# FontesLineares.net
KiCad netlist of a schematic drawn in Altium Designer
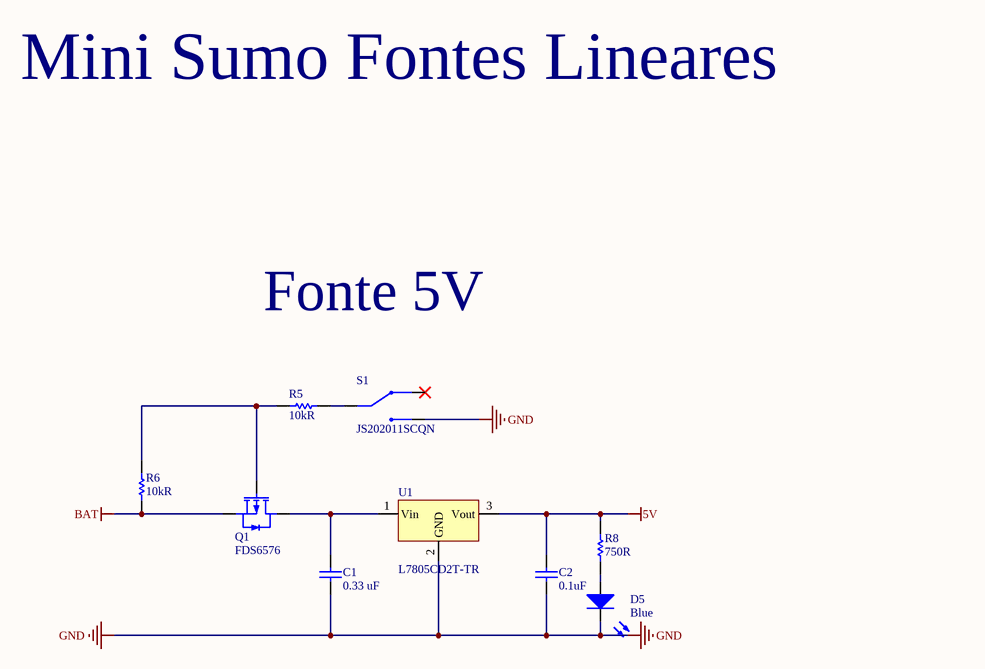
[diagram p0: FontesLineares.SchDoc]

(export (version "E")
  (design (tool "Eeschema 10.0.6"))
  (components
    (comp (ref "C1")
      (value "0.33 uF")
      (footprint "C0805")
      (description "CAP CER 0.33UF 25V X7R 0805")
      (fields
        (field (name "MANUFACTURER") "Murata Eletronics")
        (field (name "PART NUMBER") "GCM21BR71E334KA37K")
        (field (name "LIBRARY CONTROL - PERSON THAT CHECKED FOOTPRINT") "Nikaum")
        (field (name "LIBRARY CONTROL - PERSON THAT CHECKED SCHEMATIC") "Nikaum")
        (field (name "LIBRARY CONTROL - PERSON THAT DID THE LAST UPDATE FOOTPRINT") "Nikaum")
        (field (name "LIBRARY CONTROL - PERSON THAT DID THE LAST UPDATE SCHEMATIC") "Nikaum")
      )
      (libsource (lib "Uai!Tecas") (part "GCM21BR71E334KA37K"))
    )
    (comp (ref "C2")
      (value "0.1uF")
      (footprint "C0805")
      (description "CAP CER 0.1uF 25V X7R 0805")
      (fields
        (field (name "MANUFACTURER") "Kemet")
        (field (name "PART NUMBER") "C0805C104M3RACTU")
        (field (name "LIBRARY CONTROL - PERSON THAT CHECKED SCHEMATIC") "Guilherme")
        (field (name "LIBRARY CONTROL - PERSON THAT DID THE LAST UPDATE SCHEMATIC") "Marcos")
      )
      (libsource (lib "Uai!Tecas") (part "C0805C104M3RACTU"))
    )
    (comp (ref "D5")
      (value "Blue")
      (footprint "DIODO_2-SMD-3215")
      (description "LED 75mW BLUE 45MCD 3215")
      (fields
        (field (name "MANUFACTURER") "Everlight Electronics")
        (field (name "PART NUMBER") "EAST3215BA5")
        (field (name "LIBRARY CONTROL - PERSON THAT CHECKED FOOTPRINT") "Lucas")
        (field (name "LIBRARY CONTROL - PERSON THAT CHECKED SCHEMATIC") "Lucas")
        (field (name "LIBRARY CONTROL - PERSON THAT DID THE LAST UPDATE FOOTPRINT") "Stéfany (Ster)")
        (field (name "LIBRARY CONTROL - PERSON THAT DID THE LAST UPDATE SCHEMATIC") "Stéfany (Ster)")
      )
      (libsource (lib "Diodo") (part "EAST3215BA5"))
    )
    (comp (ref "Q1")
      (value "FDS6576")
      (footprint "SOIC-8")
      (description "MOSFET P-CH 20V 11A SOIC-8")
      (fields (field (name "PART NUMBER") "SOIC-8") (field (name "MANUFACTURER") "onsemi / Fairchild"))
      (libsource (lib "Uai!Tecas") (part "FDS6576"))
    )
    (comp (ref "R5")
      (value "10kR")
      (footprint "RESISTOR_0603")
      (description "RES SMD 10K OHM 5% 1/10W 0603")
      (fields
        (field (name "MANUFACTURER") "Yageo")
        (field (name "PART NUMBER") "RC0603JR-0710KL")
        (field (name "LIBRARY CONTROL - PERSON THAT CHECKED SCHEMATIC") "Marcos")
        (field (name "LIBRARY CONTROL - PERSON THAT DID THE LAST UPDATE FOOTPRINT") "Dalarme")
        (field (name "LIBRARY CONTROL - PERSON THAT DID THE LAST UPDATE SCHEMATIC") "Marcos")
      )
      (libsource (lib "Uai!Tecas") (part "RC0603JR-0710KL"))
    )
    (comp (ref "R6")
      (value "10kR")
      (footprint "RESISTOR_0603")
      (description "RES SMD 10K OHM 5% 1/10W 0603")
      (fields
        (field (name "MANUFACTURER") "Yageo")
        (field (name "PART NUMBER") "RC0603JR-0710KL")
        (field (name "LIBRARY CONTROL - PERSON THAT CHECKED SCHEMATIC") "Marcos")
        (field (name "LIBRARY CONTROL - PERSON THAT DID THE LAST UPDATE FOOTPRINT") "Dalarme")
        (field (name "LIBRARY CONTROL - PERSON THAT DID THE LAST UPDATE SCHEMATIC") "Marcos")
      )
      (libsource (lib "Uai!Tecas") (part "RC0603JR-0710KL"))
    )
    (comp (ref "R8")
      (value "750R")
      (footprint "RESISTOR_0805")
      (description "RES SMD 750 OHM 5% 1/8W 0805")
      (fields
        (field (name "MANUFACTURER") "Panasonic")
        (field (name "PART NUMBER") "ERJ-6GEYJ751V")
        (field (name "LIBRARY CONTROL - PERSON THAT CHECKED FOOTPRINT") "Nikaum")
        (field (name "LIBRARY CONTROL - PERSON THAT CHECKED SCHEMATIC") "Guilherme")
        (field (name "LIBRARY CONTROL - PERSON THAT DID THE LAST UPDATE FOOTPRINT") "Dalarme")
        (field (name "LIBRARY CONTROL - PERSON THAT DID THE LAST UPDATE SCHEMATIC") "Nikaum")
      )
      (libsource (lib "Uai!Tecas") (part "ERJ-6GEYJ751V"))
    )
    (comp (ref "S1")
      (value "JS202011SCQN")
      (footprint "DPDT")
      (description "DEEP SWITCH 4 POSITIONS")
      (fields
        (field (name "MANUFACTURER") "C&K")
        (field (name "MOUSER PART NUMBER") "611-JS202011SCQN")
        (field (name "LIBRARY CONTROL - PERSON THAT CHECKED FOOTPRINT") "Nikaum")
        (field (name "LIBRARY CONTROL - PERSON THAT CHECKED SCHEMATIC") "Nikaum")
        (field (name "LIBRARY CONTROL - PERSON THAT DID THE LAST UPDATE FOOTPRINT") "Nikaum")
        (field (name "LIBRARY CONTROL - PERSON THAT DID THE LAST UPDATE SCHEMATIC") "Nikaum")
      )
      (libsource (lib "Uai!Tecas") (part "JS202011SCQN"))
    )
    (comp (ref "U1")
      (value "L7805CD2T-TR")
      (footprint "D2PAK")
      (description "IC REG LINEAR 5V 1A D2PAK")
      (fields
        (field (name "MANUFACTURER") "ST")
        (field (name "LIBRARY CONTROL - PERSON THAT CHECKED FOOTPRINT") "Nícolas")
        (field (name "LIBRARY CONTROL - PERSON THAT CHECKED SCHEMATIC") "Nícolas")
        (field (name "LIBRARY CONTROL - PERSON THAT DID THE LAST UPDATE SCHEMATIC") "Nícolas")
      )
      (libsource (lib "Uai!Tecas") (part "L7805CD2T-TR"))
    )
  )
  (nets
    (net (code "1") (name "5V") (class "Default")
      (node (ref "C2") (pin "2") (pinfunction "2_2") (pintype "passive"))
      (node (ref "R8") (pin "2") (pinfunction "2_2") (pintype "passive"))
      (node (ref "U1") (pin "3") (pinfunction "Vout_3") (pintype "power_in"))
    )
    (net (code "2") (name "BAT") (class "Default")
      (node (ref "Q1") (pin "S") (pinfunction "S_S") (pintype "passive"))
      (node (ref "R6") (pin "1") (pinfunction "1_1") (pintype "passive"))
    )
    (net (code "3") (name "GND") (class "Default")
      (node (ref "C1") (pin "1") (pinfunction "1_1") (pintype "passive"))
      (node (ref "C2") (pin "1") (pinfunction "1_1") (pintype "passive"))
      (node (ref "D5") (pin "C") (pinfunction "C_C") (pintype "passive"))
      (node (ref "S1") (pin "A3") (pinfunction "3_A3") (pintype "passive"))
      (node (ref "U1") (pin "2") (pinfunction "GND_2") (pintype "power_in"))
    )
    (net (code "4") (name "Net-(D5-PadA)") (class "Default")
      (node (ref "D5") (pin "A") (pinfunction "A_A") (pintype "passive"))
      (node (ref "R8") (pin "1") (pinfunction "1_1") (pintype "passive"))
    )
    (net (code "5") (name "Net-(Q1-PadG)") (class "Default")
      (node (ref "Q1") (pin "G") (pinfunction "G_G") (pintype "passive"))
      (node (ref "R5") (pin "2") (pinfunction "2_2") (pintype "passive"))
      (node (ref "R6") (pin "2") (pinfunction "2_2") (pintype "passive"))
    )
    (net (code "6") (name "Net-(S1-1)") (class "Default")
      (node (ref "R5") (pin "1") (pinfunction "1_1") (pintype "passive"))
      (node (ref "S1") (pin "A1") (pinfunction "1_A1") (pintype "passive"))
    )
    (net (code "7") (name "Net-(U1-Vin)") (class "Default")
      (node (ref "C1") (pin "2") (pinfunction "2_2") (pintype "passive"))
      (node (ref "Q1") (pin "D") (pinfunction "D_D") (pintype "passive"))
      (node (ref "U1") (pin "1") (pinfunction "Vin_1") (pintype "power_in"))
    )
    (net (code "8") (name "unconnected-(S1-4-PadA2)") (class "Default")
      (node (ref "S1") (pin "A2") (pinfunction "4_A2") (pintype "passive+no_connect"))
    )
  )
)
